# digital.net
KiCad netlist of a schematic drawn in Altium Designer
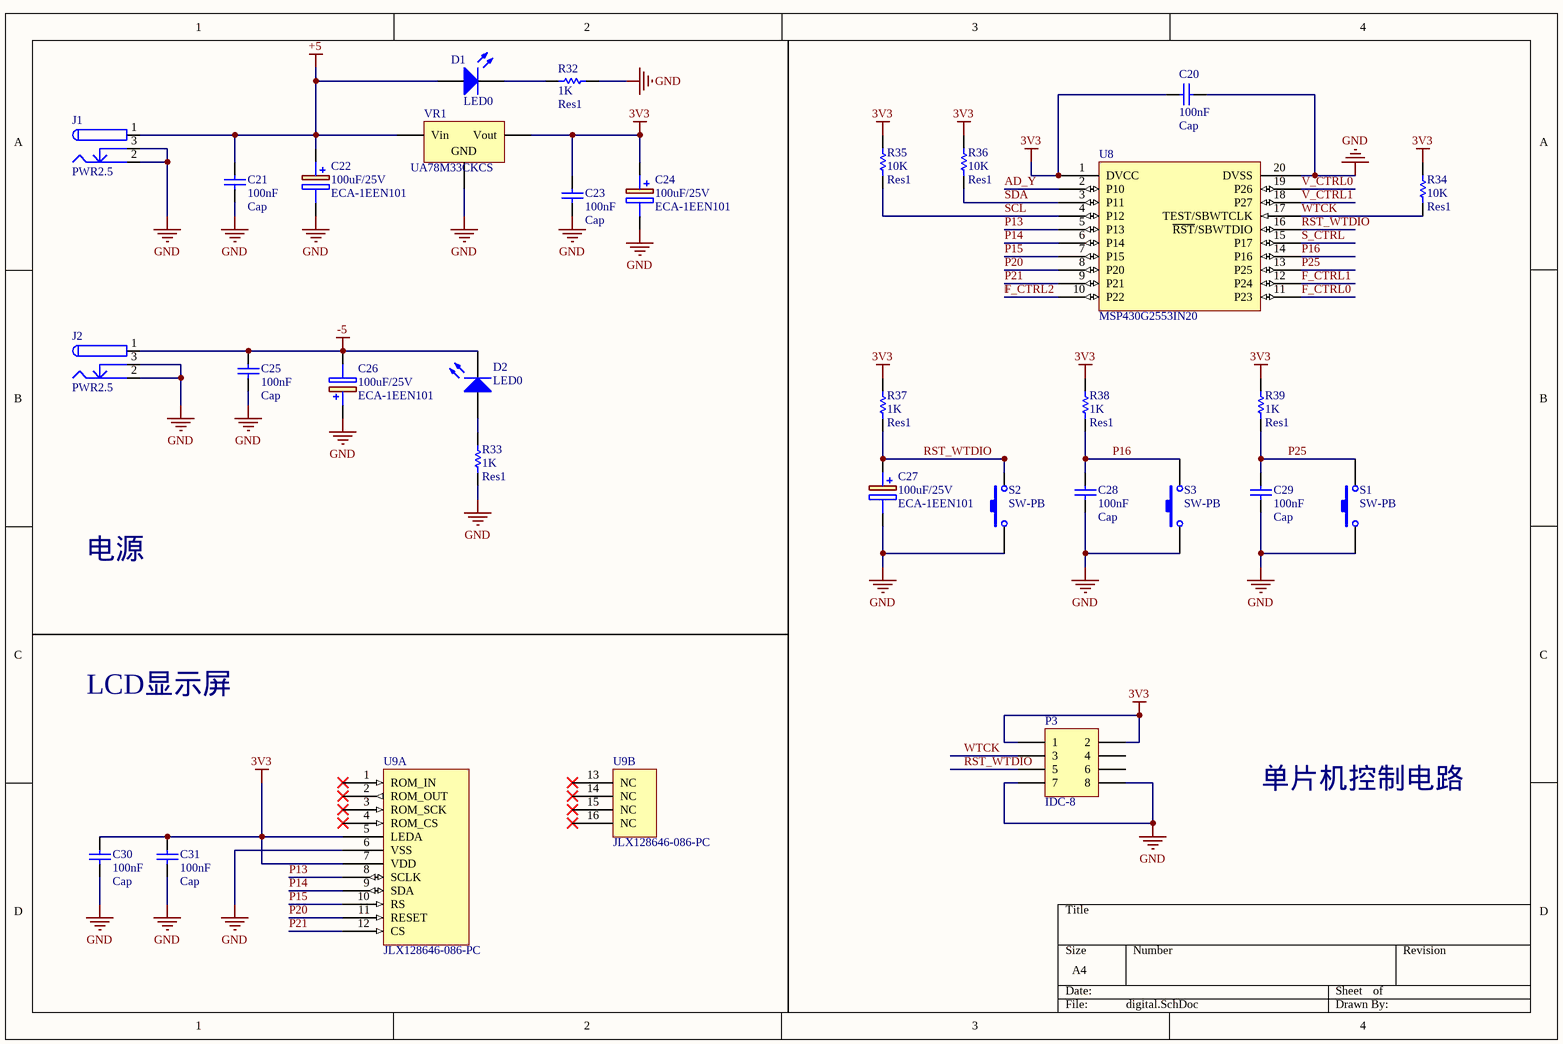
[diagram p0: digital.SchDoc]

(export (version "E")
  (design (tool "Eeschema 10.0.6"))
  (components
    (comp (ref "C20")
      (value "Cap")
      (footprint "RAD-0.2-cap")
      (description "Capacitor")
      (fields (field (name "ALTIUM_VALUE") "100nF") (field (name "PUBLISHER") "Altium Limited"))
      (libsource (lib "Lissajous") (part "Cap"))
    )
    (comp (ref "C21")
      (value "Cap")
      (footprint "RAD-0.2-cap")
      (description "Capacitor")
      (fields (field (name "ALTIUM_VALUE") "100nF") (field (name "PUBLISHER") "Altium Limited"))
      (libsource (lib "Lissajous") (part "Cap"))
    )
    (comp (ref "C22")
      (value "ECA-1EEN101")
      (footprint "CAPPRD350W65D800H1250")
      (description "Capacitor Polarised")
      (fields (field (name "MOUSER PART NUMBER") "667-ECA-1EEN101") (field (name "ALTIUM_VALUE") "100uF/25V"))
      (libsource (lib "Lissajous") (part "ECA-1EEN101"))
    )
    (comp (ref "C23")
      (value "Cap")
      (footprint "RAD-0.2-cap")
      (description "Capacitor")
      (fields (field (name "ALTIUM_VALUE") "100nF") (field (name "PUBLISHER") "Altium Limited"))
      (libsource (lib "Lissajous") (part "Cap"))
    )
    (comp (ref "C24")
      (value "ECA-1EEN101")
      (footprint "CAPPRD350W65D800H1250")
      (description "Capacitor Polarised")
      (fields (field (name "MOUSER PART NUMBER") "667-ECA-1EEN101") (field (name "ALTIUM_VALUE") "100uF/25V"))
      (libsource (lib "Lissajous") (part "ECA-1EEN101"))
    )
    (comp (ref "C25")
      (value "Cap")
      (footprint "RAD-0.2-cap")
      (description "Capacitor")
      (fields (field (name "ALTIUM_VALUE") "100nF") (field (name "PUBLISHER") "Altium Limited"))
      (libsource (lib "Lissajous") (part "Cap"))
    )
    (comp (ref "C26")
      (value "ECA-1EEN101")
      (footprint "CAPPRD350W65D800H1250")
      (description "Capacitor Polarised")
      (fields (field (name "MOUSER PART NUMBER") "667-ECA-1EEN101") (field (name "ALTIUM_VALUE") "100uF/25V"))
      (libsource (lib "") (part "ECA-1EEN101_1"))
    )
    (comp (ref "C27")
      (value "ECA-1EEN101")
      (footprint "CAPPRD350W65D800H1250")
      (description "Capacitor Polarised")
      (fields (field (name "MOUSER PART NUMBER") "667-ECA-1EEN101") (field (name "ALTIUM_VALUE") "100uF/25V"))
      (libsource (lib "Lissajous") (part "ECA-1EEN101"))
    )
    (comp (ref "C28")
      (value "Cap")
      (footprint "RAD-0.2-cap")
      (description "Capacitor")
      (fields (field (name "ALTIUM_VALUE") "100nF") (field (name "PUBLISHER") "Altium Limited"))
      (libsource (lib "Lissajous") (part "Cap"))
    )
    (comp (ref "C29")
      (value "Cap")
      (footprint "RAD-0.2-cap")
      (description "Capacitor")
      (fields (field (name "ALTIUM_VALUE") "100nF") (field (name "PUBLISHER") "Altium Limited"))
      (libsource (lib "Lissajous") (part "Cap"))
    )
    (comp (ref "C30")
      (value "Cap")
      (footprint "RAD-0.2-cap")
      (description "Capacitor")
      (fields (field (name "ALTIUM_VALUE") "100nF") (field (name "PUBLISHER") "Altium Limited"))
      (libsource (lib "Lissajous") (part "Cap"))
    )
    (comp (ref "C31")
      (value "Cap")
      (footprint "RAD-0.2-cap")
      (description "Capacitor")
      (fields (field (name "ALTIUM_VALUE") "100nF") (field (name "PUBLISHER") "Altium Limited"))
      (libsource (lib "Lissajous") (part "Cap"))
    )
    (comp (ref "D1")
      (value "LED0")
      (footprint "LED-GREEN")
      (description "Typical INFRARED GaAs LED")
      (fields (field (name "PUBLISHER") "Altium Limited"))
      (libsource (lib "Lissajous") (part "LED0"))
    )
    (comp (ref "D2")
      (value "LED0")
      (footprint "LED-GREEN")
      (description "Typical INFRARED GaAs LED")
      (fields (field (name "PUBLISHER") "Altium Limited"))
      (libsource (lib "Lissajous") (part "LED0"))
    )
    (comp (ref "J1")
      (value "PWR2.5")
      (footprint "KOBI-16PJ032_V")
      (description "Low Voltage Power Supply Connector")
      (fields (field (name "PUBLISHER") "Altium Limited"))
      (libsource (lib "Lissajous") (part "PWR2.5"))
    )
    (comp (ref "J2")
      (value "PWR2.5")
      (footprint "KOBI-16PJ032_V")
      (description "Low Voltage Power Supply Connector")
      (fields (field (name "PUBLISHER") "Altium Limited"))
      (libsource (lib "Lissajous") (part "PWR2.5"))
    )
    (comp (ref "P3")
      (value "IDC-8")
      (footprint "IDC-8")
      (description "Header, 4-Pin, Dual row")
      (fields (field (name "PUBLISHER") "Altium Limited"))
      (libsource (lib "Lissajous") (part "IDC-8"))
    )
    (comp (ref "R32")
      (value "Res1")
      (footprint "RES-AXIAL-0.4")
      (description "Resistor")
      (fields (field (name "ALTIUM_VALUE") "1K") (field (name "PUBLISHER") "Altium Limited"))
      (libsource (lib "Lissajous") (part "Res1"))
    )
    (comp (ref "R33")
      (value "Res1")
      (footprint "RES-AXIAL-0.4")
      (description "Resistor")
      (fields (field (name "ALTIUM_VALUE") "1K") (field (name "PUBLISHER") "Altium Limited"))
      (libsource (lib "Lissajous") (part "Res1"))
    )
    (comp (ref "R34")
      (value "Res1")
      (footprint "RES-AXIAL-0.4")
      (description "Resistor")
      (fields (field (name "ALTIUM_VALUE") "10K") (field (name "PUBLISHER") "Altium Limited"))
      (libsource (lib "Lissajous") (part "Res1"))
    )
    (comp (ref "R35")
      (value "Res1")
      (footprint "RES-AXIAL-0.4")
      (description "Resistor")
      (fields (field (name "ALTIUM_VALUE") "10K") (field (name "PUBLISHER") "Altium Limited"))
      (libsource (lib "Lissajous") (part "Res1"))
    )
    (comp (ref "R36")
      (value "Res1")
      (footprint "RES-AXIAL-0.4")
      (description "Resistor")
      (fields (field (name "ALTIUM_VALUE") "10K") (field (name "PUBLISHER") "Altium Limited"))
      (libsource (lib "Lissajous") (part "Res1"))
    )
    (comp (ref "R37")
      (value "Res1")
      (footprint "RES-AXIAL-0.4")
      (description "Resistor")
      (fields (field (name "ALTIUM_VALUE") "1K") (field (name "PUBLISHER") "Altium Limited"))
      (libsource (lib "Lissajous") (part "Res1"))
    )
    (comp (ref "R38")
      (value "Res1")
      (footprint "RES-AXIAL-0.4")
      (description "Resistor")
      (fields (field (name "ALTIUM_VALUE") "1K") (field (name "PUBLISHER") "Altium Limited"))
      (libsource (lib "Lissajous") (part "Res1"))
    )
    (comp (ref "R39")
      (value "Res1")
      (footprint "RES-AXIAL-0.4")
      (description "Resistor")
      (fields (field (name "ALTIUM_VALUE") "1K") (field (name "PUBLISHER") "Altium Limited"))
      (libsource (lib "Lissajous") (part "Res1"))
    )
    (comp (ref "S1")
      (value "SW-PB")
      (footprint "FSM18JH")
      (description "Switch")
      (fields (field (name "PUBLISHER") "Altium Limited"))
      (libsource (lib "Lissajous") (part "SW-PB"))
    )
    (comp (ref "S2")
      (value "SW-PB")
      (footprint "FSM18JH")
      (description "Switch")
      (fields (field (name "PUBLISHER") "Altium Limited"))
      (libsource (lib "Lissajous") (part "SW-PB"))
    )
    (comp (ref "S3")
      (value "SW-PB")
      (footprint "FSM18JH")
      (description "Switch")
      (fields (field (name "PUBLISHER") "Altium Limited"))
      (libsource (lib "Lissajous") (part "SW-PB"))
    )
    (comp (ref "U8")
      (value "MSP430G2553IN20")
      (footprint "MSP430G2553IN20 - duplicate")
      (description "混合处理器")
      (libsource (lib "zxr") (part "MSP430G2553"))
    )
    (comp (ref "U9")
      (value "JLX128646-086-PC")
      (footprint "JLX128646-086-PC")
      (description "LCD 128*64")
      (libsource (lib "zxr") (part "JLX128646-086-PC"))
    )
    (comp (ref "VR1")
      (value "UA78M33CKCS")
      (footprint "TO254P470X1016X1965-3P")
      (description "Voltage Regulator")
      (fields (field (name "PUBLISHER") "Altium Limited"))
      (libsource (lib "Lissajous") (part "UA78M33CKCS"))
    )
  )
  (nets
    (net (code "1") (name "+5") (class "Default")
      (node (ref "C21") (pin "2") (pinfunction "2_2") (pintype "passive"))
      (node (ref "C22") (pin "1") (pinfunction "+_1") (pintype "passive"))
      (node (ref "D1") (pin "1") (pinfunction "A_1") (pintype "passive"))
      (node (ref "J1") (pin "1") (pinfunction "1_1") (pintype "power_in"))
      (node (ref "VR1") (pin "1") (pinfunction "Vin_1") (pintype "passive"))
    )
    (net (code "2") (name "-5") (class "Default")
      (node (ref "C25") (pin "2") (pinfunction "2_2") (pintype "passive"))
      (node (ref "C26") (pin "2") (pinfunction "-_2") (pintype "passive"))
      (node (ref "D2") (pin "2") (pinfunction "K_2") (pintype "passive"))
      (node (ref "J2") (pin "1") (pinfunction "1_1") (pintype "power_in"))
    )
    (net (code "3") (name "/") (class "Default")
      (node (ref "U8") (pin "10") (pinfunction "P22_10") (pintype "bidirectional"))
    )
    (net (code "4") (name "/AD_Y") (class "Default")
      (node (ref "U8") (pin "2") (pinfunction "P10_2") (pintype "bidirectional"))
    )
    (net (code "5") (name "/F_CTRL0") (class "Default")
      (node (ref "U8") (pin "11") (pinfunction "P23_11") (pintype "bidirectional"))
    )
    (net (code "6") (name "/F_CTRL1") (class "Default")
      (node (ref "U8") (pin "12") (pinfunction "P24_12") (pintype "bidirectional"))
    )
    (net (code "7") (name "/P13") (class "Default")
      (node (ref "U8") (pin "5") (pinfunction "P13_5") (pintype "bidirectional"))
      (node (ref "U9") (pin "8") (pinfunction "SCLK_8") (pintype "bidirectional"))
    )
    (net (code "8") (name "/P14") (class "Default")
      (node (ref "U8") (pin "6") (pinfunction "P14_6") (pintype "bidirectional"))
      (node (ref "U9") (pin "9") (pinfunction "SDA_9") (pintype "bidirectional"))
    )
    (net (code "9") (name "/P15") (class "Default")
      (node (ref "U8") (pin "7") (pinfunction "P15_7") (pintype "bidirectional"))
      (node (ref "U9") (pin "10") (pinfunction "RS_10") (pintype "input"))
    )
    (net (code "10") (name "/P16") (class "Default")
      (node (ref "C28") (pin "2") (pinfunction "2_2") (pintype "passive"))
      (node (ref "R38") (pin "1") (pinfunction "1_1") (pintype "passive"))
      (node (ref "S3") (pin "2") (pinfunction "2_2") (pintype "passive"))
      (node (ref "U8") (pin "14") (pinfunction "P16_14") (pintype "bidirectional"))
    )
    (net (code "11") (name "/P20") (class "Default")
      (node (ref "U8") (pin "8") (pinfunction "P20_8") (pintype "bidirectional"))
      (node (ref "U9") (pin "11") (pinfunction "RESET_11") (pintype "input"))
    )
    (net (code "12") (name "/P21") (class "Default")
      (node (ref "U8") (pin "9") (pinfunction "P21_9") (pintype "bidirectional"))
      (node (ref "U9") (pin "12") (pinfunction "CS_12") (pintype "input"))
    )
    (net (code "13") (name "/P25") (class "Default")
      (node (ref "C29") (pin "2") (pinfunction "2_2") (pintype "passive"))
      (node (ref "R39") (pin "1") (pinfunction "1_1") (pintype "passive"))
      (node (ref "S1") (pin "2") (pinfunction "2_2") (pintype "passive"))
      (node (ref "U8") (pin "13") (pinfunction "P25_13") (pintype "bidirectional"))
    )
    (net (code "14") (name "/RST_WTDIO") (class "Default")
      (node (ref "C27") (pin "1") (pinfunction "+_1") (pintype "passive"))
      (node (ref "P3") (pin "5") (pinfunction "5_5") (pintype "passive"))
      (node (ref "R37") (pin "1") (pinfunction "1_1") (pintype "passive"))
      (node (ref "S2") (pin "2") (pinfunction "2_2") (pintype "passive"))
      (node (ref "U8") (pin "16") (pinfunction "~{RST}/SBWTDIO_16") (pintype "bidirectional"))
    )
    (net (code "15") (name "/SCL") (class "Default")
      (node (ref "R35") (pin "1") (pinfunction "1_1") (pintype "passive"))
      (node (ref "U8") (pin "4") (pinfunction "P12_4") (pintype "bidirectional"))
    )
    (net (code "16") (name "/SDA") (class "Default")
      (node (ref "R36") (pin "1") (pinfunction "1_1") (pintype "passive"))
      (node (ref "U8") (pin "3") (pinfunction "P11_3") (pintype "bidirectional"))
    )
    (net (code "17") (name "/S_CTRL") (class "Default")
      (node (ref "U8") (pin "15") (pinfunction "P17_15") (pintype "bidirectional"))
    )
    (net (code "18") (name "/V_CTRL0") (class "Default")
      (node (ref "U8") (pin "19") (pinfunction "P26_19") (pintype "bidirectional"))
    )
    (net (code "19") (name "/V_CTRL1") (class "Default")
      (node (ref "U8") (pin "18") (pinfunction "P27_18") (pintype "bidirectional"))
    )
    (net (code "20") (name "/WTCK") (class "Default")
      (node (ref "P3") (pin "3") (pinfunction "3_3") (pintype "passive"))
      (node (ref "R34") (pin "1") (pinfunction "1_1") (pintype "passive"))
      (node (ref "U8") (pin "17") (pinfunction "TEST/SBWTCLK_17") (pintype "input"))
    )
    (net (code "21") (name "3V3") (class "Default")
      (node (ref "C20") (pin "1") (pinfunction "1_1") (pintype "passive"))
      (node (ref "C23") (pin "2") (pinfunction "2_2") (pintype "passive"))
      (node (ref "C24") (pin "1") (pinfunction "+_1") (pintype "passive"))
      (node (ref "C30") (pin "2") (pinfunction "2_2") (pintype "passive"))
      (node (ref "C31") (pin "1") (pinfunction "1_1") (pintype "passive"))
      (node (ref "P3") (pin "1") (pinfunction "1_1") (pintype "passive"))
      (node (ref "P3") (pin "2") (pinfunction "2_2") (pintype "passive"))
      (node (ref "R34") (pin "2") (pinfunction "2_2") (pintype "passive"))
      (node (ref "R35") (pin "2") (pinfunction "2_2") (pintype "passive"))
      (node (ref "R36") (pin "2") (pinfunction "2_2") (pintype "passive"))
      (node (ref "R37") (pin "2") (pinfunction "2_2") (pintype "passive"))
      (node (ref "R38") (pin "2") (pinfunction "2_2") (pintype "passive"))
      (node (ref "R39") (pin "2") (pinfunction "2_2") (pintype "passive"))
      (node (ref "U8") (pin "1") (pinfunction "DVCC_1") (pintype "power_in"))
      (node (ref "U9") (pin "5") (pinfunction "LEDA_5") (pintype "power_in"))
      (node (ref "U9") (pin "7") (pinfunction "VDD_7") (pintype "power_in"))
      (node (ref "VR1") (pin "3") (pinfunction "Vout_3") (pintype "passive"))
    )
    (net (code "22") (name "GND") (class "Default")
      (node (ref "C20") (pin "2") (pinfunction "2_2") (pintype "passive"))
      (node (ref "C21") (pin "1") (pinfunction "1_1") (pintype "passive"))
      (node (ref "C22") (pin "2") (pinfunction "-_2") (pintype "passive"))
      (node (ref "C23") (pin "1") (pinfunction "1_1") (pintype "passive"))
      (node (ref "C24") (pin "2") (pinfunction "-_2") (pintype "passive"))
      (node (ref "C25") (pin "1") (pinfunction "1_1") (pintype "passive"))
      (node (ref "C26") (pin "1") (pinfunction "+_1") (pintype "passive"))
      (node (ref "C27") (pin "2") (pinfunction "-_2") (pintype "passive"))
      (node (ref "C28") (pin "1") (pinfunction "1_1") (pintype "passive"))
      (node (ref "C29") (pin "1") (pinfunction "1_1") (pintype "passive"))
      (node (ref "C30") (pin "1") (pinfunction "1_1") (pintype "passive"))
      (node (ref "C31") (pin "2") (pinfunction "2_2") (pintype "passive"))
      (node (ref "J1") (pin "2") (pinfunction "2_2") (pintype "power_in"))
      (node (ref "J1") (pin "3") (pinfunction "3_3") (pintype "power_in"))
      (node (ref "J2") (pin "2") (pinfunction "2_2") (pintype "power_in"))
      (node (ref "J2") (pin "3") (pinfunction "3_3") (pintype "power_in"))
      (node (ref "P3") (pin "7") (pinfunction "7_7") (pintype "passive"))
      (node (ref "P3") (pin "8") (pinfunction "8_8") (pintype "passive"))
      (node (ref "R32") (pin "2") (pinfunction "2_2") (pintype "passive"))
      (node (ref "R33") (pin "1") (pinfunction "1_1") (pintype "passive"))
      (node (ref "S1") (pin "1") (pinfunction "1_1") (pintype "passive"))
      (node (ref "S2") (pin "1") (pinfunction "1_1") (pintype "passive"))
      (node (ref "S3") (pin "1") (pinfunction "1_1") (pintype "passive"))
      (node (ref "U8") (pin "20") (pinfunction "DVSS_20") (pintype "power_in"))
      (node (ref "U9") (pin "6") (pinfunction "VSS_6") (pintype "power_in"))
      (node (ref "VR1") (pin "2") (pinfunction "GND_2") (pintype "passive"))
    )
    (net (code "23") (name "Net-(D1-K)") (class "Default")
      (node (ref "D1") (pin "2") (pinfunction "K_2") (pintype "passive"))
      (node (ref "R32") (pin "1") (pinfunction "1_1") (pintype "passive"))
    )
    (net (code "24") (name "Net-(D2-A)") (class "Default")
      (node (ref "D2") (pin "1") (pinfunction "A_1") (pintype "passive"))
      (node (ref "R33") (pin "2") (pinfunction "2_2") (pintype "passive"))
    )
    (net (code "25") (name "unconnected-(P3-Pad4)") (class "Default")
      (node (ref "P3") (pin "4") (pinfunction "4_4") (pintype "passive"))
    )
    (net (code "26") (name "unconnected-(P3-Pad6)") (class "Default")
      (node (ref "P3") (pin "6") (pinfunction "6_6") (pintype "passive"))
    )
    (net (code "27") (name "unconnected-(U9A-ROM_CS-Pad4)") (class "Default")
      (node (ref "U9") (pin "4") (pinfunction "ROM_CS_4") (pintype "input+no_connect"))
    )
    (net (code "28") (name "unconnected-(U9A-ROM_IN-Pad1)") (class "Default")
      (node (ref "U9") (pin "1") (pinfunction "ROM_IN_1") (pintype "input+no_connect"))
    )
    (net (code "29") (name "unconnected-(U9A-ROM_OUT-Pad2)") (class "Default")
      (node (ref "U9") (pin "2") (pinfunction "ROM_OUT_2") (pintype "output+no_connect"))
    )
    (net (code "30") (name "unconnected-(U9A-ROM_SCK-Pad3)") (class "Default")
      (node (ref "U9") (pin "3") (pinfunction "ROM_SCK_3") (pintype "input+no_connect"))
    )
    (net (code "31") (name "unconnected-(U9B-NC-Pad13)") (class "Default")
      (node (ref "U9") (pin "13") (pinfunction "NC_13") (pintype "passive+no_connect"))
    )
    (net (code "32") (name "unconnected-(U9B-NC-Pad14)") (class "Default")
      (node (ref "U9") (pin "14") (pinfunction "NC_14") (pintype "passive+no_connect"))
    )
    (net (code "33") (name "unconnected-(U9B-NC-Pad15)") (class "Default")
      (node (ref "U9") (pin "15") (pinfunction "NC_15") (pintype "passive+no_connect"))
    )
    (net (code "34") (name "unconnected-(U9B-NC-Pad16)") (class "Default")
      (node (ref "U9") (pin "16") (pinfunction "NC_16") (pintype "passive+no_connect"))
    )
  )
)
